# IRF7455_IC.net
KiCad netlist of a schematic drawn in Altium Designer
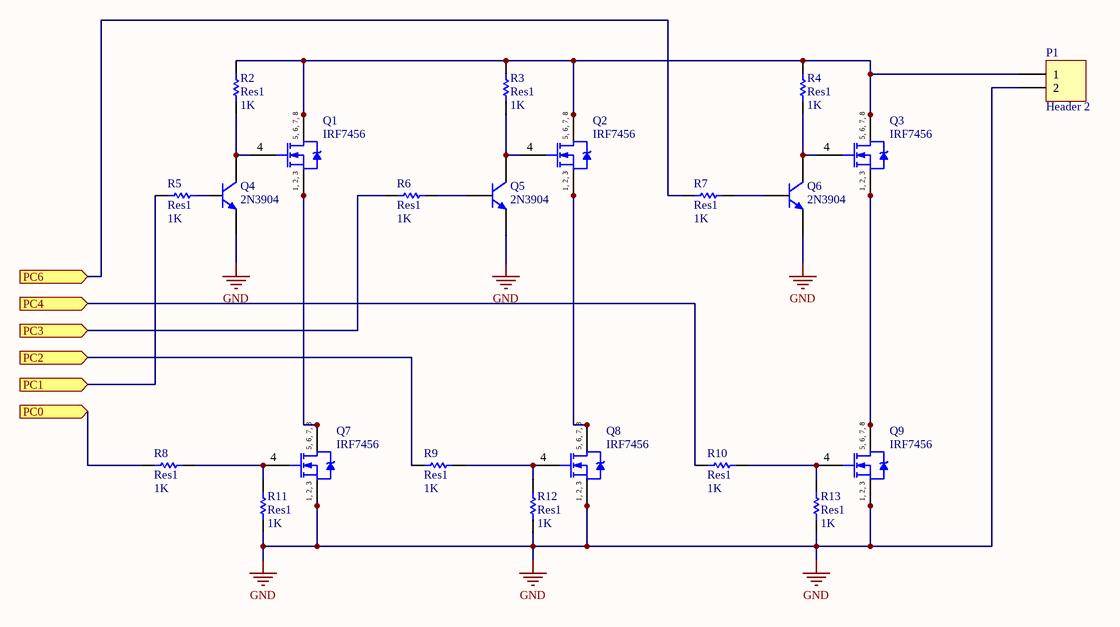
[diagram p0: IRF7455 IC.SchDoc]

(export (version "E")
  (design (tool "Eeschema 10.0.6"))
  (components
    (comp (ref "P1")
      (value "Header 2")
      (footprint "HDR1X2")
      (description "Header, 2-Pin")
      (fields (field (name "PUBLISHER") "Altium Limited"))
      (libsource (lib "Miscellaneous Connectors") (part "Header 2"))
    )
    (comp (ref "Q1")
      (value "IRF7456")
      (footprint "SO-8_N")
      (description "HEXFET Power MOSFET")
      (fields (field (name "PUBLISHER") "Altium Limited"))
      (libsource (lib "IR Discrete MOSFET - Power") (part "IRF7456"))
    )
    (comp (ref "Q2")
      (value "IRF7456")
      (footprint "SO-8_N")
      (description "HEXFET Power MOSFET")
      (fields (field (name "PUBLISHER") "Altium Limited"))
      (libsource (lib "IR Discrete MOSFET - Power") (part "IRF7456"))
    )
    (comp (ref "Q3")
      (value "IRF7456")
      (footprint "SO-8_N")
      (description "HEXFET Power MOSFET")
      (fields (field (name "PUBLISHER") "Altium Limited"))
      (libsource (lib "IR Discrete MOSFET - Power") (part "IRF7456"))
    )
    (comp (ref "Q4")
      (value "2N3904")
      (footprint "TO-92A")
      (description "NPN General Purpose Amplifier")
      (fields (field (name "PUBLISHER") "Altium Limited"))
      (libsource (lib "Miscellaneous Devices") (part "2N3904"))
    )
    (comp (ref "Q5")
      (value "2N3904")
      (footprint "TO-92A")
      (description "NPN General Purpose Amplifier")
      (fields (field (name "PUBLISHER") "Altium Limited"))
      (libsource (lib "Miscellaneous Devices") (part "2N3904"))
    )
    (comp (ref "Q6")
      (value "2N3904")
      (footprint "TO-92A")
      (description "NPN General Purpose Amplifier")
      (fields (field (name "PUBLISHER") "Altium Limited"))
      (libsource (lib "Miscellaneous Devices") (part "2N3904"))
    )
    (comp (ref "Q7")
      (value "IRF7456")
      (footprint "SO-8_N")
      (description "HEXFET Power MOSFET")
      (fields (field (name "PUBLISHER") "Altium Limited"))
      (libsource (lib "IR Discrete MOSFET - Power") (part "IRF7456"))
    )
    (comp (ref "Q8")
      (value "IRF7456")
      (footprint "SO-8_N")
      (description "HEXFET Power MOSFET")
      (fields (field (name "PUBLISHER") "Altium Limited"))
      (libsource (lib "IR Discrete MOSFET - Power") (part "IRF7456"))
    )
    (comp (ref "Q9")
      (value "IRF7456")
      (footprint "SO-8_N")
      (description "HEXFET Power MOSFET")
      (fields (field (name "PUBLISHER") "Altium Limited"))
      (libsource (lib "IR Discrete MOSFET - Power") (part "IRF7456"))
    )
    (comp (ref "R2")
      (value "Res1")
      (footprint "AXIAL-0.3")
      (description "Resistor")
      (fields (field (name "ALTIUM_VALUE") "1K") (field (name "PUBLISHER") "Altium Limited"))
      (libsource (lib "Miscellaneous Devices") (part "Res1"))
    )
    (comp (ref "R3")
      (value "Res1")
      (footprint "AXIAL-0.3")
      (description "Resistor")
      (fields (field (name "ALTIUM_VALUE") "1K") (field (name "PUBLISHER") "Altium Limited"))
      (libsource (lib "Miscellaneous Devices") (part "Res1"))
    )
    (comp (ref "R4")
      (value "Res1")
      (footprint "AXIAL-0.3")
      (description "Resistor")
      (fields (field (name "ALTIUM_VALUE") "1K") (field (name "PUBLISHER") "Altium Limited"))
      (libsource (lib "Miscellaneous Devices") (part "Res1"))
    )
    (comp (ref "R5")
      (value "Res1")
      (footprint "AXIAL-0.3")
      (description "Resistor")
      (fields (field (name "ALTIUM_VALUE") "1K") (field (name "PUBLISHER") "Altium Limited"))
      (libsource (lib "Miscellaneous Devices") (part "Res1"))
    )
    (comp (ref "R6")
      (value "Res1")
      (footprint "AXIAL-0.3")
      (description "Resistor")
      (fields (field (name "ALTIUM_VALUE") "1K") (field (name "PUBLISHER") "Altium Limited"))
      (libsource (lib "Miscellaneous Devices") (part "Res1"))
    )
    (comp (ref "R7")
      (value "Res1")
      (footprint "AXIAL-0.3")
      (description "Resistor")
      (fields (field (name "ALTIUM_VALUE") "1K") (field (name "PUBLISHER") "Altium Limited"))
      (libsource (lib "Miscellaneous Devices") (part "Res1"))
    )
    (comp (ref "R8")
      (value "Res1")
      (footprint "AXIAL-0.3")
      (description "Resistor")
      (fields (field (name "ALTIUM_VALUE") "1K") (field (name "PUBLISHER") "Altium Limited"))
      (libsource (lib "Miscellaneous Devices") (part "Res1"))
    )
    (comp (ref "R9")
      (value "Res1")
      (footprint "AXIAL-0.3")
      (description "Resistor")
      (fields (field (name "ALTIUM_VALUE") "1K") (field (name "PUBLISHER") "Altium Limited"))
      (libsource (lib "Miscellaneous Devices") (part "Res1"))
    )
    (comp (ref "R10")
      (value "Res1")
      (footprint "AXIAL-0.3")
      (description "Resistor")
      (fields (field (name "ALTIUM_VALUE") "1K") (field (name "PUBLISHER") "Altium Limited"))
      (libsource (lib "Miscellaneous Devices") (part "Res1"))
    )
    (comp (ref "R11")
      (value "Res1")
      (footprint "AXIAL-0.3")
      (description "Resistor")
      (fields (field (name "ALTIUM_VALUE") "1K") (field (name "PUBLISHER") "Altium Limited"))
      (libsource (lib "Miscellaneous Devices") (part "Res1"))
    )
    (comp (ref "R12")
      (value "Res1")
      (footprint "AXIAL-0.3")
      (description "Resistor")
      (fields (field (name "ALTIUM_VALUE") "1K") (field (name "PUBLISHER") "Altium Limited"))
      (libsource (lib "Miscellaneous Devices") (part "Res1"))
    )
    (comp (ref "R13")
      (value "Res1")
      (footprint "AXIAL-0.3")
      (description "Resistor")
      (fields (field (name "ALTIUM_VALUE") "1K") (field (name "PUBLISHER") "Altium Limited"))
      (libsource (lib "Miscellaneous Devices") (part "Res1"))
    )
  )
  (nets
    (net (code "1") (name "/PC0") (class "Default")
      (node (ref "R8") (pin "2") (pinfunction "2_2") (pintype "passive"))
    )
    (net (code "2") (name "/PC1") (class "Default")
      (node (ref "R5") (pin "2") (pinfunction "2_2") (pintype "passive"))
    )
    (net (code "3") (name "/PC2") (class "Default")
      (node (ref "R9") (pin "2") (pinfunction "2_2") (pintype "passive"))
    )
    (net (code "4") (name "/PC3") (class "Default")
      (node (ref "R6") (pin "2") (pinfunction "2_2") (pintype "passive"))
    )
    (net (code "5") (name "/PC4") (class "Default")
      (node (ref "R10") (pin "2") (pinfunction "2_2") (pintype "passive"))
    )
    (net (code "6") (name "/PC6") (class "Default")
      (node (ref "R7") (pin "2") (pinfunction "2_2") (pintype "passive"))
    )
    (net (code "7") (name "GND") (class "Default")
      (node (ref "P1") (pin "2") (pinfunction "2_2") (pintype "passive"))
      (node (ref "Q4") (pin "1") (pinfunction "E_1") (pintype "passive"))
      (node (ref "Q5") (pin "1") (pinfunction "E_1") (pintype "passive"))
      (node (ref "Q6") (pin "1") (pinfunction "E_1") (pintype "passive"))
      (node (ref "Q7") (pin "1") (pinfunction "S_1") (pintype "passive"))
      (node (ref "Q7") (pin "2") (pinfunction "S_2") (pintype "passive"))
      (node (ref "Q7") (pin "3") (pinfunction "S_3") (pintype "passive"))
      (node (ref "Q8") (pin "1") (pinfunction "S_1") (pintype "passive"))
      (node (ref "Q8") (pin "2") (pinfunction "S_2") (pintype "passive"))
      (node (ref "Q8") (pin "3") (pinfunction "S_3") (pintype "passive"))
      (node (ref "Q9") (pin "1") (pinfunction "S_1") (pintype "passive"))
      (node (ref "Q9") (pin "2") (pinfunction "S_2") (pintype "passive"))
      (node (ref "Q9") (pin "3") (pinfunction "S_3") (pintype "passive"))
      (node (ref "R11") (pin "1") (pinfunction "1_1") (pintype "passive"))
      (node (ref "R12") (pin "1") (pinfunction "1_1") (pintype "passive"))
      (node (ref "R13") (pin "1") (pinfunction "1_1") (pintype "passive"))
    )
    (net (code "8") (name "Net-(P1-Pad1)") (class "Default")
      (node (ref "P1") (pin "1") (pinfunction "1_1") (pintype "passive"))
      (node (ref "Q1") (pin "5") (pinfunction "D_5") (pintype "passive"))
      (node (ref "Q1") (pin "6") (pinfunction "D_6") (pintype "passive"))
      (node (ref "Q1") (pin "7") (pinfunction "D_7") (pintype "passive"))
      (node (ref "Q1") (pin "8") (pinfunction "D_8") (pintype "passive"))
      (node (ref "Q2") (pin "5") (pinfunction "D_5") (pintype "passive"))
      (node (ref "Q2") (pin "6") (pinfunction "D_6") (pintype "passive"))
      (node (ref "Q2") (pin "7") (pinfunction "D_7") (pintype "passive"))
      (node (ref "Q2") (pin "8") (pinfunction "D_8") (pintype "passive"))
      (node (ref "Q3") (pin "5") (pinfunction "D_5") (pintype "passive"))
      (node (ref "Q3") (pin "6") (pinfunction "D_6") (pintype "passive"))
      (node (ref "Q3") (pin "7") (pinfunction "D_7") (pintype "passive"))
      (node (ref "Q3") (pin "8") (pinfunction "D_8") (pintype "passive"))
      (node (ref "R2") (pin "2") (pinfunction "2_2") (pintype "passive"))
      (node (ref "R3") (pin "2") (pinfunction "2_2") (pintype "passive"))
      (node (ref "R4") (pin "2") (pinfunction "2_2") (pintype "passive"))
    )
    (net (code "9") (name "Net-(Q1-G)") (class "Default")
      (node (ref "Q1") (pin "4") (pinfunction "G_4") (pintype "passive"))
      (node (ref "Q4") (pin "3") (pinfunction "C_3") (pintype "passive"))
      (node (ref "R2") (pin "1") (pinfunction "1_1") (pintype "passive"))
    )
    (net (code "10") (name "Net-(Q1-S-Pad1)") (class "Default")
      (node (ref "Q1") (pin "1") (pinfunction "S_1") (pintype "passive"))
      (node (ref "Q1") (pin "2") (pinfunction "S_2") (pintype "passive"))
      (node (ref "Q1") (pin "3") (pinfunction "S_3") (pintype "passive"))
      (node (ref "Q7") (pin "5") (pinfunction "D_5") (pintype "passive"))
      (node (ref "Q7") (pin "6") (pinfunction "D_6") (pintype "passive"))
      (node (ref "Q7") (pin "7") (pinfunction "D_7") (pintype "passive"))
      (node (ref "Q7") (pin "8") (pinfunction "D_8") (pintype "passive"))
    )
    (net (code "11") (name "Net-(Q2-G)") (class "Default")
      (node (ref "Q2") (pin "4") (pinfunction "G_4") (pintype "passive"))
      (node (ref "Q5") (pin "3") (pinfunction "C_3") (pintype "passive"))
      (node (ref "R3") (pin "1") (pinfunction "1_1") (pintype "passive"))
    )
    (net (code "12") (name "Net-(Q2-S-Pad1)") (class "Default")
      (node (ref "Q2") (pin "1") (pinfunction "S_1") (pintype "passive"))
      (node (ref "Q2") (pin "2") (pinfunction "S_2") (pintype "passive"))
      (node (ref "Q2") (pin "3") (pinfunction "S_3") (pintype "passive"))
      (node (ref "Q8") (pin "5") (pinfunction "D_5") (pintype "passive"))
      (node (ref "Q8") (pin "6") (pinfunction "D_6") (pintype "passive"))
      (node (ref "Q8") (pin "7") (pinfunction "D_7") (pintype "passive"))
      (node (ref "Q8") (pin "8") (pinfunction "D_8") (pintype "passive"))
    )
    (net (code "13") (name "Net-(Q3-G)") (class "Default")
      (node (ref "Q3") (pin "4") (pinfunction "G_4") (pintype "passive"))
      (node (ref "Q6") (pin "3") (pinfunction "C_3") (pintype "passive"))
      (node (ref "R4") (pin "1") (pinfunction "1_1") (pintype "passive"))
    )
    (net (code "14") (name "Net-(Q3-S-Pad1)") (class "Default")
      (node (ref "Q3") (pin "1") (pinfunction "S_1") (pintype "passive"))
      (node (ref "Q3") (pin "2") (pinfunction "S_2") (pintype "passive"))
      (node (ref "Q3") (pin "3") (pinfunction "S_3") (pintype "passive"))
      (node (ref "Q9") (pin "5") (pinfunction "D_5") (pintype "passive"))
      (node (ref "Q9") (pin "6") (pinfunction "D_6") (pintype "passive"))
      (node (ref "Q9") (pin "7") (pinfunction "D_7") (pintype "passive"))
      (node (ref "Q9") (pin "8") (pinfunction "D_8") (pintype "passive"))
    )
    (net (code "15") (name "Net-(Q4-B)") (class "Default")
      (node (ref "Q4") (pin "2") (pinfunction "B_2") (pintype "passive"))
      (node (ref "R5") (pin "1") (pinfunction "1_1") (pintype "passive"))
    )
    (net (code "16") (name "Net-(Q5-B)") (class "Default")
      (node (ref "Q5") (pin "2") (pinfunction "B_2") (pintype "passive"))
      (node (ref "R6") (pin "1") (pinfunction "1_1") (pintype "passive"))
    )
    (net (code "17") (name "Net-(Q6-B)") (class "Default")
      (node (ref "Q6") (pin "2") (pinfunction "B_2") (pintype "passive"))
      (node (ref "R7") (pin "1") (pinfunction "1_1") (pintype "passive"))
    )
    (net (code "18") (name "Net-(Q7-G)") (class "Default")
      (node (ref "Q7") (pin "4") (pinfunction "G_4") (pintype "passive"))
      (node (ref "R11") (pin "2") (pinfunction "2_2") (pintype "passive"))
      (node (ref "R8") (pin "1") (pinfunction "1_1") (pintype "passive"))
    )
    (net (code "19") (name "Net-(Q8-G)") (class "Default")
      (node (ref "Q8") (pin "4") (pinfunction "G_4") (pintype "passive"))
      (node (ref "R12") (pin "2") (pinfunction "2_2") (pintype "passive"))
      (node (ref "R9") (pin "1") (pinfunction "1_1") (pintype "passive"))
    )
    (net (code "20") (name "Net-(Q9-G)") (class "Default")
      (node (ref "Q9") (pin "4") (pinfunction "G_4") (pintype "passive"))
      (node (ref "R10") (pin "1") (pinfunction "1_1") (pintype "passive"))
      (node (ref "R13") (pin "2") (pinfunction "2_2") (pintype "passive"))
    )
  )
)
